# nixie_ticker.net
KiCad netlist of a schematic drawn in EAGLE
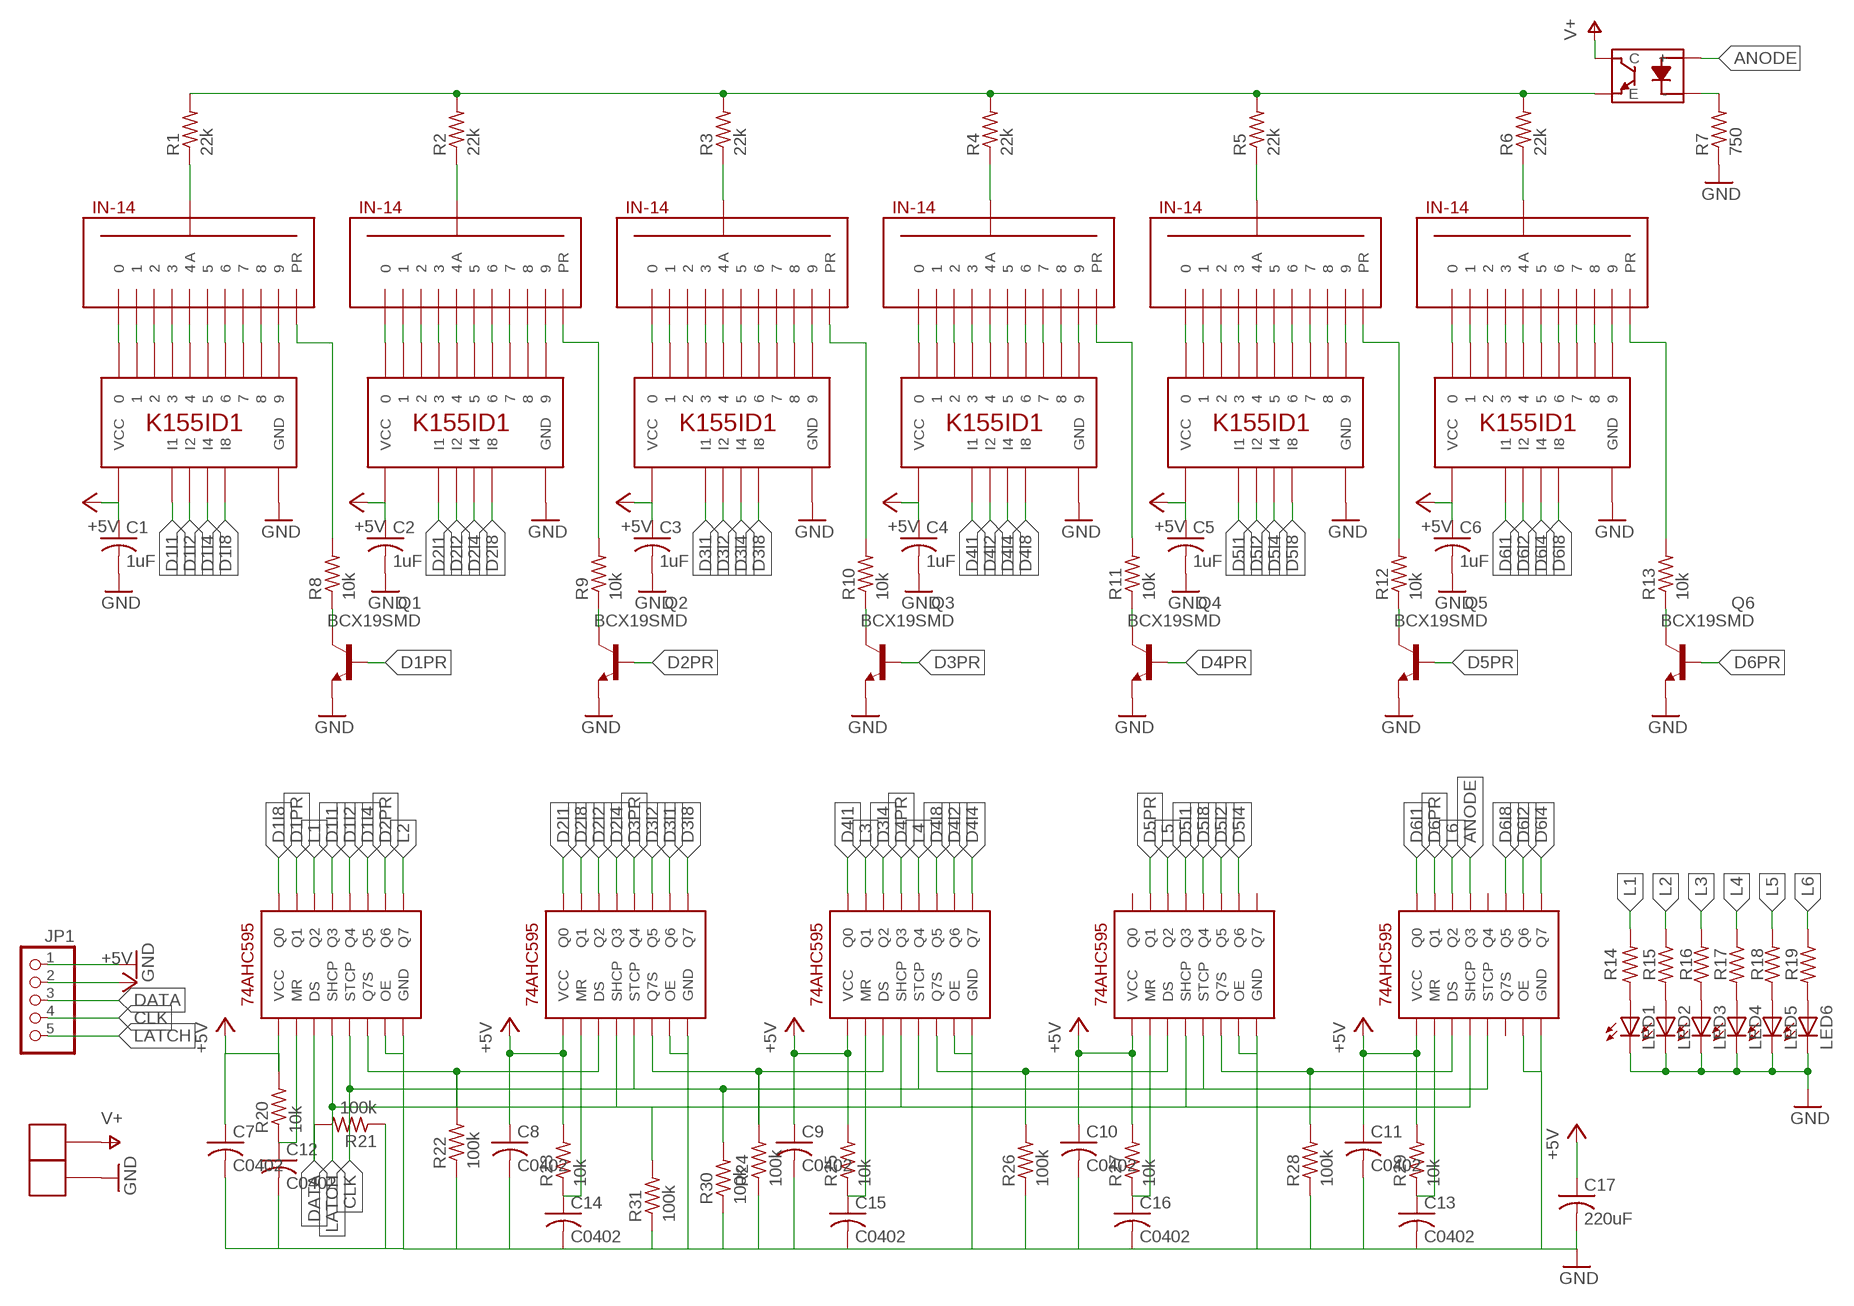
[diagram p0: schematic, sheet 1]

(export (version "E")
  (design (tool "Eeschema 10.0.6"))
  (components
    (comp (ref "C1")
      (value "1uF")
      (footprint "eagle-import:C0402")
      (libsource (lib "eagle-import") (part "C0402"))
    )
    (comp (ref "C2")
      (value "1uF")
      (footprint "eagle-import:C0402")
      (libsource (lib "eagle-import") (part "C0402"))
    )
    (comp (ref "C3")
      (value "1uF")
      (footprint "eagle-import:C0402")
      (libsource (lib "eagle-import") (part "C0402"))
    )
    (comp (ref "C4")
      (value "1uF")
      (footprint "eagle-import:C0402")
      (libsource (lib "eagle-import") (part "C0402"))
    )
    (comp (ref "C5")
      (value "1uF")
      (footprint "eagle-import:C0402")
      (libsource (lib "eagle-import") (part "C0402"))
    )
    (comp (ref "C6")
      (value "1uF")
      (footprint "eagle-import:C0402")
      (libsource (lib "eagle-import") (part "C0402"))
    )
    (comp (ref "C7")
      (value "C0402")
      (footprint "eagle-import:C0402")
      (libsource (lib "eagle-import") (part "C0402"))
    )
    (comp (ref "C8")
      (value "C0402")
      (footprint "eagle-import:C0402")
      (libsource (lib "eagle-import") (part "C0402"))
    )
    (comp (ref "C9")
      (value "C0402")
      (footprint "eagle-import:C0402")
      (libsource (lib "eagle-import") (part "C0402"))
    )
    (comp (ref "C10")
      (value "C0402")
      (footprint "eagle-import:C0402")
      (libsource (lib "eagle-import") (part "C0402"))
    )
    (comp (ref "C11")
      (value "C0402")
      (footprint "eagle-import:C0402")
      (libsource (lib "eagle-import") (part "C0402"))
    )
    (comp (ref "C12")
      (value "C0402")
      (footprint "eagle-import:C0402")
      (libsource (lib "eagle-import") (part "C0402"))
    )
    (comp (ref "C13")
      (value "C0402")
      (footprint "eagle-import:C0402")
      (libsource (lib "eagle-import") (part "C0402"))
    )
    (comp (ref "C14")
      (value "C0402")
      (footprint "eagle-import:C0402")
      (libsource (lib "eagle-import") (part "C0402"))
    )
    (comp (ref "C15")
      (value "C0402")
      (footprint "eagle-import:C0402")
      (libsource (lib "eagle-import") (part "C0402"))
    )
    (comp (ref "C16")
      (value "C0402")
      (footprint "eagle-import:C0402")
      (libsource (lib "eagle-import") (part "C0402"))
    )
    (comp (ref "C17")
      (value "220uF")
      (footprint "eagle-import:CAPAE830X1050")
      (libsource (lib "eagle-import") (part "UUR1C221MCL6GS"))
    )
    (comp (ref "JP1")
      (value "PINHD-1X5")
      (footprint "eagle-import:1X05")
      (libsource (lib "eagle-import") (part "PINHD-1X5"))
    )
    (comp (ref "JP2")
      (value "ZKFDS")
      (footprint "eagle-import:ZKFDS")
      (libsource (lib "eagle-import") (part "ZKFDS"))
    )
    (comp (ref "JP3")
      (value "ZKFDS")
      (footprint "eagle-import:ZKFDS")
      (libsource (lib "eagle-import") (part "ZKFDS"))
    )
    (comp (ref "LED1")
      (value "LEDCHIP-LED0603")
      (footprint "eagle-import:CHIP-LED0603")
      (libsource (lib "eagle-import") (part "LEDCHIP-LED0603"))
    )
    (comp (ref "LED2")
      (value "LEDCHIP-LED0603")
      (footprint "eagle-import:CHIP-LED0603")
      (libsource (lib "eagle-import") (part "LEDCHIP-LED0603"))
    )
    (comp (ref "LED3")
      (value "LEDCHIP-LED0603")
      (footprint "eagle-import:CHIP-LED0603")
      (libsource (lib "eagle-import") (part "LEDCHIP-LED0603"))
    )
    (comp (ref "LED4")
      (value "LEDCHIP-LED0603")
      (footprint "eagle-import:CHIP-LED0603")
      (libsource (lib "eagle-import") (part "LEDCHIP-LED0603"))
    )
    (comp (ref "LED5")
      (value "LEDCHIP-LED0603")
      (footprint "eagle-import:CHIP-LED0603")
      (libsource (lib "eagle-import") (part "LEDCHIP-LED0603"))
    )
    (comp (ref "LED6")
      (value "LEDCHIP-LED0603")
      (footprint "eagle-import:CHIP-LED0603")
      (libsource (lib "eagle-import") (part "LEDCHIP-LED0603"))
    )
    (comp (ref "N1")
      (value "IN14_12PIN12PIN")
      (footprint "eagle-import:IN14-12PIN")
      (libsource (lib "eagle-import") (part "IN14_12PIN12PIN"))
    )
    (comp (ref "N2")
      (value "IN14_12PIN12PIN")
      (footprint "eagle-import:IN14-12PIN")
      (libsource (lib "eagle-import") (part "IN14_12PIN12PIN"))
    )
    (comp (ref "N3")
      (value "IN14_12PIN12PIN")
      (footprint "eagle-import:IN14-12PIN")
      (libsource (lib "eagle-import") (part "IN14_12PIN12PIN"))
    )
    (comp (ref "N4")
      (value "IN14_12PIN12PIN")
      (footprint "eagle-import:IN14-12PIN")
      (libsource (lib "eagle-import") (part "IN14_12PIN12PIN"))
    )
    (comp (ref "N5")
      (value "IN14_12PIN12PIN")
      (footprint "eagle-import:IN14-12PIN")
      (libsource (lib "eagle-import") (part "IN14_12PIN12PIN"))
    )
    (comp (ref "N6")
      (value "IN14_12PIN12PIN")
      (footprint "eagle-import:IN14-12PIN")
      (libsource (lib "eagle-import") (part "IN14_12PIN12PIN"))
    )
    (comp (ref "Q1")
      (value "BCX19SMD")
      (footprint "eagle-import:SOT23-BEC")
      (libsource (lib "eagle-import") (part "BCX19SMD"))
    )
    (comp (ref "Q2")
      (value "BCX19SMD")
      (footprint "eagle-import:SOT23-BEC")
      (libsource (lib "eagle-import") (part "BCX19SMD"))
    )
    (comp (ref "Q3")
      (value "BCX19SMD")
      (footprint "eagle-import:SOT23-BEC")
      (libsource (lib "eagle-import") (part "BCX19SMD"))
    )
    (comp (ref "Q4")
      (value "BCX19SMD")
      (footprint "eagle-import:SOT23-BEC")
      (libsource (lib "eagle-import") (part "BCX19SMD"))
    )
    (comp (ref "Q5")
      (value "BCX19SMD")
      (footprint "eagle-import:SOT23-BEC")
      (libsource (lib "eagle-import") (part "BCX19SMD"))
    )
    (comp (ref "Q6")
      (value "BCX19SMD")
      (footprint "eagle-import:SOT23-BEC")
      (libsource (lib "eagle-import") (part "BCX19SMD"))
    )
    (comp (ref "R1")
      (value "22k")
      (footprint "eagle-import:R1206")
      (libsource (lib "eagle-import") (part "R-US_R1206"))
    )
    (comp (ref "R2")
      (value "22k")
      (footprint "eagle-import:R1206")
      (libsource (lib "eagle-import") (part "R-US_R1206"))
    )
    (comp (ref "R3")
      (value "22k")
      (footprint "eagle-import:R1206")
      (libsource (lib "eagle-import") (part "R-US_R1206"))
    )
    (comp (ref "R4")
      (value "22k")
      (footprint "eagle-import:R1206")
      (libsource (lib "eagle-import") (part "R-US_R1206"))
    )
    (comp (ref "R5")
      (value "22k")
      (footprint "eagle-import:R1206")
      (libsource (lib "eagle-import") (part "R-US_R1206"))
    )
    (comp (ref "R6")
      (value "22k")
      (footprint "eagle-import:R1206")
      (libsource (lib "eagle-import") (part "R-US_R1206"))
    )
    (comp (ref "R7")
      (value "750")
      (footprint "eagle-import:R0603")
      (libsource (lib "eagle-import") (part "R-US_R0603"))
    )
    (comp (ref "R8")
      (value "10k")
      (footprint "eagle-import:R0805")
      (libsource (lib "eagle-import") (part "R-US_R0805"))
    )
    (comp (ref "R9")
      (value "10k")
      (footprint "eagle-import:R0805")
      (libsource (lib "eagle-import") (part "R-US_R0805"))
    )
    (comp (ref "R10")
      (value "10k")
      (footprint "eagle-import:R0805")
      (libsource (lib "eagle-import") (part "R-US_R0805"))
    )
    (comp (ref "R11")
      (value "10k")
      (footprint "eagle-import:R0805")
      (libsource (lib "eagle-import") (part "R-US_R0805"))
    )
    (comp (ref "R12")
      (value "10k")
      (footprint "eagle-import:R0805")
      (libsource (lib "eagle-import") (part "R-US_R0805"))
    )
    (comp (ref "R13")
      (value "10k")
      (footprint "eagle-import:R0805")
      (libsource (lib "eagle-import") (part "R-US_R0805"))
    )
    (comp (ref "R14")
      (value "R-US_R0805")
      (footprint "eagle-import:R0805")
      (libsource (lib "eagle-import") (part "R-US_R0805"))
    )
    (comp (ref "R15")
      (value "R-US_R0805")
      (footprint "eagle-import:R0805")
      (libsource (lib "eagle-import") (part "R-US_R0805"))
    )
    (comp (ref "R16")
      (value "R-US_R0805")
      (footprint "eagle-import:R0805")
      (libsource (lib "eagle-import") (part "R-US_R0805"))
    )
    (comp (ref "R17")
      (value "R-US_R0805")
      (footprint "eagle-import:R0805")
      (libsource (lib "eagle-import") (part "R-US_R0805"))
    )
    (comp (ref "R18")
      (value "R-US_R0805")
      (footprint "eagle-import:R0805")
      (libsource (lib "eagle-import") (part "R-US_R0805"))
    )
    (comp (ref "R19")
      (value "R-US_R0805")
      (footprint "eagle-import:R0805")
      (libsource (lib "eagle-import") (part "R-US_R0805"))
    )
    (comp (ref "R20")
      (value "10k")
      (footprint "eagle-import:R0402")
      (libsource (lib "eagle-import") (part "R0402"))
    )
    (comp (ref "R21")
      (value "100k")
      (footprint "eagle-import:R0402")
      (libsource (lib "eagle-import") (part "R0402"))
    )
    (comp (ref "R22")
      (value "100k")
      (footprint "eagle-import:R0402")
      (libsource (lib "eagle-import") (part "R0402"))
    )
    (comp (ref "R23")
      (value "10k")
      (footprint "eagle-import:R0402")
      (libsource (lib "eagle-import") (part "R0402"))
    )
    (comp (ref "R24")
      (value "100k")
      (footprint "eagle-import:R0402")
      (libsource (lib "eagle-import") (part "R0402"))
    )
    (comp (ref "R25")
      (value "10k")
      (footprint "eagle-import:R0402")
      (libsource (lib "eagle-import") (part "R0402"))
    )
    (comp (ref "R26")
      (value "100k")
      (footprint "eagle-import:R0402")
      (libsource (lib "eagle-import") (part "R0402"))
    )
    (comp (ref "R27")
      (value "10k")
      (footprint "eagle-import:R0402")
      (libsource (lib "eagle-import") (part "R0402"))
    )
    (comp (ref "R28")
      (value "100k")
      (footprint "eagle-import:R0402")
      (libsource (lib "eagle-import") (part "R0402"))
    )
    (comp (ref "R29")
      (value "10k")
      (footprint "eagle-import:R0402")
      (libsource (lib "eagle-import") (part "R0402"))
    )
    (comp (ref "R30")
      (value "100k")
      (footprint "eagle-import:R0402")
      (libsource (lib "eagle-import") (part "R0402"))
    )
    (comp (ref "R31")
      (value "100k")
      (footprint "eagle-import:R0402")
      (libsource (lib "eagle-import") (part "R0402"))
    )
    (comp (ref "U1")
      (value "TLP3873D")
      (footprint "eagle-import:SOP254P1000X215-4")
      (libsource (lib "eagle-import") (part "TLP3873D"))
    )
    (comp (ref "U2")
      (value "K155ID1")
      (footprint "eagle-import:DIP-16_SMD")
      (libsource (lib "eagle-import") (part "K155ID1"))
    )
    (comp (ref "U3")
      (value "K155ID1")
      (footprint "eagle-import:DIP-16_SMD")
      (libsource (lib "eagle-import") (part "K155ID1"))
    )
    (comp (ref "U4")
      (value "K155ID1")
      (footprint "eagle-import:DIP-16_SMD")
      (libsource (lib "eagle-import") (part "K155ID1"))
    )
    (comp (ref "U5")
      (value "K155ID1")
      (footprint "eagle-import:DIP-16_SMD")
      (libsource (lib "eagle-import") (part "K155ID1"))
    )
    (comp (ref "U6")
      (value "K155ID1")
      (footprint "eagle-import:DIP-16_SMD")
      (libsource (lib "eagle-import") (part "K155ID1"))
    )
    (comp (ref "U7")
      (value "K155ID1")
      (footprint "eagle-import:DIP-16_SMD")
      (libsource (lib "eagle-import") (part "K155ID1"))
    )
    (comp (ref "U8")
      (value "74AHC595")
      (footprint "eagle-import:16SOIC")
      (libsource (lib "eagle-import") (part "74AHC595"))
    )
    (comp (ref "U9")
      (value "74AHC595")
      (footprint "eagle-import:16SOIC")
      (libsource (lib "eagle-import") (part "74AHC595"))
    )
    (comp (ref "U10")
      (value "74AHC595")
      (footprint "eagle-import:16SOIC")
      (libsource (lib "eagle-import") (part "74AHC595"))
    )
    (comp (ref "U11")
      (value "74AHC595")
      (footprint "eagle-import:16SOIC")
      (libsource (lib "eagle-import") (part "74AHC595"))
    )
    (comp (ref "U12")
      (value "74AHC595")
      (footprint "eagle-import:16SOIC")
      (libsource (lib "eagle-import") (part "74AHC595"))
    )
  )
  (nets
    (net (code "1") (name "+5V") (class "Default")
      (node (ref "C1") (pin "1") (pinfunction "+_1") (pintype "passive"))
      (node (ref "C10") (pin "1") (pinfunction "+_1") (pintype "passive"))
      (node (ref "C11") (pin "1") (pinfunction "+_1") (pintype "passive"))
      (node (ref "C17") (pin "1") (pinfunction "+_1") (pintype "passive"))
      (node (ref "C2") (pin "1") (pinfunction "+_1") (pintype "passive"))
      (node (ref "C3") (pin "1") (pinfunction "+_1") (pintype "passive"))
      (node (ref "C4") (pin "1") (pinfunction "+_1") (pintype "passive"))
      (node (ref "C5") (pin "1") (pinfunction "+_1") (pintype "passive"))
      (node (ref "C6") (pin "1") (pinfunction "+_1") (pintype "passive"))
      (node (ref "C7") (pin "1") (pinfunction "+_1") (pintype "passive"))
      (node (ref "C8") (pin "1") (pinfunction "+_1") (pintype "passive"))
      (node (ref "C9") (pin "1") (pinfunction "+_1") (pintype "passive"))
      (node (ref "JP1") (pin "2") (pinfunction "2_2") (pintype "passive"))
      (node (ref "R20") (pin "2") (pinfunction "2_2") (pintype "passive"))
      (node (ref "R23") (pin "2") (pinfunction "2_2") (pintype "passive"))
      (node (ref "R25") (pin "2") (pinfunction "2_2") (pintype "passive"))
      (node (ref "R27") (pin "2") (pinfunction "2_2") (pintype "passive"))
      (node (ref "R29") (pin "2") (pinfunction "2_2") (pintype "passive"))
      (node (ref "U10") (pin "P$16") (pinfunction "VCC_P$16") (pintype "bidirectional"))
      (node (ref "U11") (pin "P$16") (pinfunction "VCC_P$16") (pintype "bidirectional"))
      (node (ref "U12") (pin "P$16") (pinfunction "VCC_P$16") (pintype "bidirectional"))
      (node (ref "U2") (pin "P$5") (pinfunction "VCC_P$5") (pintype "bidirectional"))
      (node (ref "U3") (pin "P$5") (pinfunction "VCC_P$5") (pintype "bidirectional"))
      (node (ref "U4") (pin "P$5") (pinfunction "VCC_P$5") (pintype "bidirectional"))
      (node (ref "U5") (pin "P$5") (pinfunction "VCC_P$5") (pintype "bidirectional"))
      (node (ref "U6") (pin "P$5") (pinfunction "VCC_P$5") (pintype "bidirectional"))
      (node (ref "U7") (pin "P$5") (pinfunction "VCC_P$5") (pintype "bidirectional"))
      (node (ref "U8") (pin "P$16") (pinfunction "VCC_P$16") (pintype "bidirectional"))
      (node (ref "U9") (pin "P$16") (pinfunction "VCC_P$16") (pintype "bidirectional"))
    )
    (net (code "2") (name "ANODE") (class "Default")
      (node (ref "U1") (pin "1") (pinfunction "+_1") (pintype "bidirectional"))
      (node (ref "U12") (pin "P$3") (pinfunction "Q3_P$3") (pintype "bidirectional"))
    )
    (net (code "3") (name "CLK") (class "Default")
      (node (ref "JP1") (pin "4") (pinfunction "4_4") (pintype "passive"))
      (node (ref "R30") (pin "2") (pinfunction "2_2") (pintype "passive"))
      (node (ref "U10") (pin "P$12") (pinfunction "STCP_P$12") (pintype "bidirectional"))
      (node (ref "U11") (pin "P$12") (pinfunction "STCP_P$12") (pintype "bidirectional"))
      (node (ref "U12") (pin "P$12") (pinfunction "STCP_P$12") (pintype "bidirectional"))
      (node (ref "U8") (pin "P$12") (pinfunction "STCP_P$12") (pintype "bidirectional"))
      (node (ref "U9") (pin "P$12") (pinfunction "STCP_P$12") (pintype "bidirectional"))
    )
    (net (code "4") (name "D1I1") (class "Default")
      (node (ref "U2") (pin "P$3") (pinfunction "I1_P$3") (pintype "bidirectional"))
      (node (ref "U8") (pin "P$3") (pinfunction "Q3_P$3") (pintype "bidirectional"))
    )
    (net (code "5") (name "D1I2") (class "Default")
      (node (ref "U2") (pin "P$6") (pinfunction "I2_P$6") (pintype "bidirectional"))
      (node (ref "U8") (pin "P$4") (pinfunction "Q4_P$4") (pintype "bidirectional"))
    )
    (net (code "6") (name "D1I4") (class "Default")
      (node (ref "U2") (pin "P$7") (pinfunction "I4_P$7") (pintype "bidirectional"))
      (node (ref "U8") (pin "P$5") (pinfunction "Q5_P$5") (pintype "bidirectional"))
    )
    (net (code "7") (name "D1I8") (class "Default")
      (node (ref "U2") (pin "P$4") (pinfunction "I8_P$4") (pintype "bidirectional"))
      (node (ref "U8") (pin "P$15") (pinfunction "Q0_P$15") (pintype "bidirectional"))
    )
    (net (code "8") (name "D1PR") (class "Default")
      (node (ref "Q1") (pin "B") (pinfunction "B_B") (pintype "passive"))
      (node (ref "U8") (pin "P$1") (pinfunction "Q1_P$1") (pintype "bidirectional"))
    )
    (net (code "9") (name "D2I1") (class "Default")
      (node (ref "U3") (pin "P$3") (pinfunction "I1_P$3") (pintype "bidirectional"))
      (node (ref "U9") (pin "P$15") (pinfunction "Q0_P$15") (pintype "bidirectional"))
    )
    (net (code "10") (name "D2I2") (class "Default")
      (node (ref "U3") (pin "P$6") (pinfunction "I2_P$6") (pintype "bidirectional"))
      (node (ref "U9") (pin "P$2") (pinfunction "Q2_P$2") (pintype "bidirectional"))
    )
    (net (code "11") (name "D2I4") (class "Default")
      (node (ref "U3") (pin "P$7") (pinfunction "I4_P$7") (pintype "bidirectional"))
      (node (ref "U9") (pin "P$3") (pinfunction "Q3_P$3") (pintype "bidirectional"))
    )
    (net (code "12") (name "D2I8") (class "Default")
      (node (ref "U3") (pin "P$4") (pinfunction "I8_P$4") (pintype "bidirectional"))
      (node (ref "U9") (pin "P$1") (pinfunction "Q1_P$1") (pintype "bidirectional"))
    )
    (net (code "13") (name "D2PR") (class "Default")
      (node (ref "Q2") (pin "B") (pinfunction "B_B") (pintype "passive"))
      (node (ref "U8") (pin "P$6") (pinfunction "Q6_P$6") (pintype "bidirectional"))
    )
    (net (code "14") (name "D3I1") (class "Default")
      (node (ref "U4") (pin "P$3") (pinfunction "I1_P$3") (pintype "bidirectional"))
      (node (ref "U9") (pin "P$6") (pinfunction "Q6_P$6") (pintype "bidirectional"))
    )
    (net (code "15") (name "D3I2") (class "Default")
      (node (ref "U4") (pin "P$6") (pinfunction "I2_P$6") (pintype "bidirectional"))
      (node (ref "U9") (pin "P$5") (pinfunction "Q5_P$5") (pintype "bidirectional"))
    )
    (net (code "16") (name "D3I4") (class "Default")
      (node (ref "U10") (pin "P$2") (pinfunction "Q2_P$2") (pintype "bidirectional"))
      (node (ref "U4") (pin "P$7") (pinfunction "I4_P$7") (pintype "bidirectional"))
    )
    (net (code "17") (name "D3I8") (class "Default")
      (node (ref "U4") (pin "P$4") (pinfunction "I8_P$4") (pintype "bidirectional"))
      (node (ref "U9") (pin "P$7") (pinfunction "Q7_P$7") (pintype "bidirectional"))
    )
    (net (code "18") (name "D3PR") (class "Default")
      (node (ref "Q3") (pin "B") (pinfunction "B_B") (pintype "passive"))
      (node (ref "U9") (pin "P$4") (pinfunction "Q4_P$4") (pintype "bidirectional"))
    )
    (net (code "19") (name "D4I1") (class "Default")
      (node (ref "U10") (pin "P$15") (pinfunction "Q0_P$15") (pintype "bidirectional"))
      (node (ref "U5") (pin "P$3") (pinfunction "I1_P$3") (pintype "bidirectional"))
    )
    (net (code "20") (name "D4I2") (class "Default")
      (node (ref "U10") (pin "P$6") (pinfunction "Q6_P$6") (pintype "bidirectional"))
      (node (ref "U5") (pin "P$6") (pinfunction "I2_P$6") (pintype "bidirectional"))
    )
    (net (code "21") (name "D4I4") (class "Default")
      (node (ref "U10") (pin "P$7") (pinfunction "Q7_P$7") (pintype "bidirectional"))
      (node (ref "U5") (pin "P$7") (pinfunction "I4_P$7") (pintype "bidirectional"))
    )
    (net (code "22") (name "D4I8") (class "Default")
      (node (ref "U10") (pin "P$5") (pinfunction "Q5_P$5") (pintype "bidirectional"))
      (node (ref "U5") (pin "P$4") (pinfunction "I8_P$4") (pintype "bidirectional"))
    )
    (net (code "23") (name "D4PR") (class "Default")
      (node (ref "Q4") (pin "B") (pinfunction "B_B") (pintype "passive"))
      (node (ref "U10") (pin "P$3") (pinfunction "Q3_P$3") (pintype "bidirectional"))
    )
    (net (code "24") (name "D5I1") (class "Default")
      (node (ref "U11") (pin "P$3") (pinfunction "Q3_P$3") (pintype "bidirectional"))
      (node (ref "U6") (pin "P$3") (pinfunction "I1_P$3") (pintype "bidirectional"))
    )
    (net (code "25") (name "D5I2") (class "Default")
      (node (ref "U11") (pin "P$5") (pinfunction "Q5_P$5") (pintype "bidirectional"))
      (node (ref "U6") (pin "P$6") (pinfunction "I2_P$6") (pintype "bidirectional"))
    )
    (net (code "26") (name "D5I4") (class "Default")
      (node (ref "U11") (pin "P$6") (pinfunction "Q6_P$6") (pintype "bidirectional"))
      (node (ref "U6") (pin "P$7") (pinfunction "I4_P$7") (pintype "bidirectional"))
    )
    (net (code "27") (name "D5I8") (class "Default")
      (node (ref "U11") (pin "P$4") (pinfunction "Q4_P$4") (pintype "bidirectional"))
      (node (ref "U6") (pin "P$4") (pinfunction "I8_P$4") (pintype "bidirectional"))
    )
    (net (code "28") (name "D5PR") (class "Default")
      (node (ref "Q5") (pin "B") (pinfunction "B_B") (pintype "passive"))
      (node (ref "U11") (pin "P$1") (pinfunction "Q1_P$1") (pintype "bidirectional"))
    )
    (net (code "29") (name "D6I1") (class "Default")
      (node (ref "U12") (pin "P$15") (pinfunction "Q0_P$15") (pintype "bidirectional"))
      (node (ref "U7") (pin "P$3") (pinfunction "I1_P$3") (pintype "bidirectional"))
    )
    (net (code "30") (name "D6I2") (class "Default")
      (node (ref "U12") (pin "P$6") (pinfunction "Q6_P$6") (pintype "bidirectional"))
      (node (ref "U7") (pin "P$6") (pinfunction "I2_P$6") (pintype "bidirectional"))
    )
    (net (code "31") (name "D6I4") (class "Default")
      (node (ref "U12") (pin "P$7") (pinfunction "Q7_P$7") (pintype "bidirectional"))
      (node (ref "U7") (pin "P$7") (pinfunction "I4_P$7") (pintype "bidirectional"))
    )
    (net (code "32") (name "D6I8") (class "Default")
      (node (ref "U12") (pin "P$5") (pinfunction "Q5_P$5") (pintype "bidirectional"))
      (node (ref "U7") (pin "P$4") (pinfunction "I8_P$4") (pintype "bidirectional"))
    )
    (net (code "33") (name "D6PR") (class "Default")
      (node (ref "Q6") (pin "B") (pinfunction "B_B") (pintype "passive"))
      (node (ref "U12") (pin "P$1") (pinfunction "Q1_P$1") (pintype "bidirectional"))
    )
    (net (code "34") (name "DATA") (class "Default")
      (node (ref "JP1") (pin "3") (pinfunction "3_3") (pintype "passive"))
      (node (ref "R21") (pin "2") (pinfunction "2_2") (pintype "passive"))
      (node (ref "U8") (pin "P$14") (pinfunction "DS_P$14") (pintype "bidirectional"))
    )
    (net (code "35") (name "GND") (class "Default")
      (node (ref "C1") (pin "2") (pinfunction "-_2") (pintype "passive"))
      (node (ref "C10") (pin "2") (pinfunction "-_2") (pintype "passive"))
      (node (ref "C11") (pin "2") (pinfunction "-_2") (pintype "passive"))
      (node (ref "C12") (pin "2") (pinfunction "-_2") (pintype "passive"))
      (node (ref "C13") (pin "2") (pinfunction "-_2") (pintype "passive"))
      (node (ref "C14") (pin "2") (pinfunction "-_2") (pintype "passive"))
      (node (ref "C15") (pin "2") (pinfunction "-_2") (pintype "passive"))
      (node (ref "C16") (pin "2") (pinfunction "-_2") (pintype "passive"))
      (node (ref "C17") (pin "2") (pinfunction "-_2") (pintype "passive"))
      (node (ref "C2") (pin "2") (pinfunction "-_2") (pintype "passive"))
      (node (ref "C3") (pin "2") (pinfunction "-_2") (pintype "passive"))
      (node (ref "C4") (pin "2") (pinfunction "-_2") (pintype "passive"))
      (node (ref "C5") (pin "2") (pinfunction "-_2") (pintype "passive"))
      (node (ref "C6") (pin "2") (pinfunction "-_2") (pintype "passive"))
      (node (ref "C7") (pin "2") (pinfunction "-_2") (pintype "passive"))
      (node (ref "C8") (pin "2") (pinfunction "-_2") (pintype "passive"))
      (node (ref "C9") (pin "2") (pinfunction "-_2") (pintype "passive"))
      (node (ref "JP1") (pin "1") (pinfunction "1_1") (pintype "passive"))
      (node (ref "JP3") (pin "P$1") (pinfunction "P$1_P$1") (pintype "bidirectional"))
      (node (ref "JP3") (pin "P$2") (pinfunction "P$1_P$2") (pintype "bidirectional"))
      (node (ref "LED1") (pin "C") (pinfunction "C_C") (pintype "passive"))
      (node (ref "LED2") (pin "C") (pinfunction "C_C") (pintype "passive"))
      (node (ref "LED3") (pin "C") (pinfunction "C_C") (pintype "passive"))
      (node (ref "LED4") (pin "C") (pinfunction "C_C") (pintype "passive"))
      (node (ref "LED5") (pin "C") (pinfunction "C_C") (pintype "passive"))
      (node (ref "LED6") (pin "C") (pinfunction "C_C") (pintype "passive"))
      (node (ref "Q1") (pin "E") (pinfunction "E_E") (pintype "passive"))
      (node (ref "Q2") (pin "E") (pinfunction "E_E") (pintype "passive"))
      (node (ref "Q3") (pin "E") (pinfunction "E_E") (pintype "passive"))
      (node (ref "Q4") (pin "E") (pinfunction "E_E") (pintype "passive"))
      (node (ref "Q5") (pin "E") (pinfunction "E_E") (pintype "passive"))
      (node (ref "Q6") (pin "E") (pinfunction "E_E") (pintype "passive"))
      (node (ref "R21") (pin "1") (pinfunction "1_1") (pintype "passive"))
      (node (ref "R22") (pin "1") (pinfunction "1_1") (pintype "passive"))
      (node (ref "R24") (pin "1") (pinfunction "1_1") (pintype "passive"))
      (node (ref "R26") (pin "1") (pinfunction "1_1") (pintype "passive"))
      (node (ref "R28") (pin "1") (pinfunction "1_1") (pintype "passive"))
      (node (ref "R30") (pin "1") (pinfunction "1_1") (pintype "passive"))
      (node (ref "R31") (pin "1") (pinfunction "1_1") (pintype "passive"))
      (node (ref "R7") (pin "1") (pinfunction "1_1") (pintype "passive"))
      (node (ref "U10") (pin "P$13") (pinfunction "OE_P$13") (pintype "bidirectional"))
      (node (ref "U10") (pin "P$8") (pinfunction "GND_P$8") (pintype "bidirectional"))
      (node (ref "U11") (pin "P$13") (pinfunction "OE_P$13") (pintype "bidirectional"))
      (node (ref "U11") (pin "P$8") (pinfunction "GND_P$8") (pintype "bidirectional"))
      (node (ref "U12") (pin "P$13") (pinfunction "OE_P$13") (pintype "bidirectional"))
      (node (ref "U12") (pin "P$8") (pinfunction "GND_P$8") (pintype "bidirectional"))
      (node (ref "U2") (pin "P$12") (pinfunction "GND_P$12") (pintype "bidirectional"))
      (node (ref "U3") (pin "P$12") (pinfunction "GND_P$12") (pintype "bidirectional"))
      (node (ref "U4") (pin "P$12") (pinfunction "GND_P$12") (pintype "bidirectional"))
      (node (ref "U5") (pin "P$12") (pinfunction "GND_P$12") (pintype "bidirectional"))
      (node (ref "U6") (pin "P$12") (pinfunction "GND_P$12") (pintype "bidirectional"))
      (node (ref "U7") (pin "P$12") (pinfunction "GND_P$12") (pintype "bidirectional"))
      (node (ref "U8") (pin "P$13") (pinfunction "OE_P$13") (pintype "bidirectional"))
      (node (ref "U8") (pin "P$8") (pinfunction "GND_P$8") (pintype "bidirectional"))
      (node (ref "U9") (pin "P$13") (pinfunction "OE_P$13") (pintype "bidirectional"))
      (node (ref "U9") (pin "P$8") (pinfunction "GND_P$8") (pintype "bidirectional"))
    )
    (net (code "36") (name "L1") (class "Default")
      (node (ref "R14") (pin "2") (pinfunction "2_2") (pintype "passive"))
      (node (ref "U8") (pin "P$2") (pinfunction "Q2_P$2") (pintype "bidirectional"))
    )
    (net (code "37") (name "L2") (class "Default")
      (node (ref "R15") (pin "1") (pinfunction "1_1") (pintype "passive"))
      (node (ref "U8") (pin "P$7") (pinfunction "Q7_P$7") (pintype "bidirectional"))
    )
    (net (code "38") (name "L3") (class "Default")
      (node (ref "R16") (pin "2") (pinfunction "2_2") (pintype "passive"))
      (node (ref "U10") (pin "P$1") (pinfunction "Q1_P$1") (pintype "bidirectional"))
    )
    (net (code "39") (name "L4") (class "Default")
      (node (ref "R17") (pin "1") (pinfunction "1_1") (pintype "passive"))
      (node (ref "U10") (pin "P$4") (pinfunction "Q4_P$4") (pintype "bidirectional"))
    )
    (net (code "40") (name "L5") (class "Default")
      (node (ref "R18") (pin "2") (pinfunction "2_2") (pintype "passive"))
      (node (ref "U11") (pin "P$2") (pinfunction "Q2_P$2") (pintype "bidirectional"))
    )
    (net (code "41") (name "L6") (class "Default")
      (node (ref "R19") (pin "1") (pinfunction "1_1") (pintype "passive"))
      (node (ref "U12") (pin "P$2") (pinfunction "Q2_P$2") (pintype "bidirectional"))
    )
    (net (code "42") (name "LATCH") (class "Default")
      (node (ref "JP1") (pin "5") (pinfunction "5_5") (pintype "passive"))
      (node (ref "R31") (pin "2") (pinfunction "2_2") (pintype "passive"))
      (node (ref "U10") (pin "P$11") (pinfunction "SHCP_P$11") (pintype "bidirectional"))
      (node (ref "U11") (pin "P$11") (pinfunction "SHCP_P$11") (pintype "bidirectional"))
      (node (ref "U12") (pin "P$11") (pinfunction "SHCP_P$11") (pintype "bidirectional"))
      (node (ref "U8") (pin "P$11") (pinfunction "SHCP_P$11") (pintype "bidirectional"))
      (node (ref "U9") (pin "P$11") (pinfunction "SHCP_P$11") (pintype "bidirectional"))
    )
    (net (code "43") (name "Net-(C12-+)") (class "Default")
      (node (ref "C12") (pin "1") (pinfunction "+_1") (pintype "passive"))
      (node (ref "R20") (pin "1") (pinfunction "1_1") (pintype "passive"))
      (node (ref "U8") (pin "P$10") (pinfunction "MR_P$10") (pintype "bidirectional"))
    )
    (net (code "44") (name "Net-(C13-+)") (class "Default")
      (node (ref "C13") (pin "1") (pinfunction "+_1") (pintype "passive"))
      (node (ref "R29") (pin "1") (pinfunction "1_1") (pintype "passive"))
      (node (ref "U12") (pin "P$10") (pinfunction "MR_P$10") (pintype "bidirectional"))
    )
    (net (code "45") (name "Net-(C14-+)") (class "Default")
      (node (ref "C14") (pin "1") (pinfunction "+_1") (pintype "passive"))
      (node (ref "R23") (pin "1") (pinfunction "1_1") (pintype "passive"))
      (node (ref "U9") (pin "P$10") (pinfunction "MR_P$10") (pintype "bidirectional"))
    )
    (net (code "46") (name "Net-(C15-+)") (class "Default")
      (node (ref "C15") (pin "1") (pinfunction "+_1") (pintype "passive"))
      (node (ref "R25") (pin "1") (pinfunction "1_1") (pintype "passive"))
      (node (ref "U10") (pin "P$10") (pinfunction "MR_P$10") (pintype "bidirectional"))
    )
    (net (code "47") (name "Net-(C16-+)") (class "Default")
      (node (ref "C16") (pin "1") (pinfunction "+_1") (pintype "passive"))
      (node (ref "R27") (pin "1") (pinfunction "1_1") (pintype "passive"))
      (node (ref "U11") (pin "P$10") (pinfunction "MR_P$10") (pintype "bidirectional"))
    )
    (net (code "48") (name "Net-(LED1-PadA)") (class "Default")
      (node (ref "LED1") (pin "A") (pinfunction "A_A") (pintype "passive"))
      (node (ref "R14") (pin "1") (pinfunction "1_1") (pintype "passive"))
    )
    (net (code "49") (name "Net-(LED2-PadA)") (class "Default")
      (node (ref "LED2") (pin "A") (pinfunction "A_A") (pintype "passive"))
      (node (ref "R15") (pin "2") (pinfunction "2_2") (pintype "passive"))
    )
    (net (code "50") (name "Net-(LED3-PadA)") (class "Default")
      (node (ref "LED3") (pin "A") (pinfunction "A_A") (pintype "passive"))
      (node (ref "R16") (pin "1") (pinfunction "1_1") (pintype "passive"))
    )
    (net (code "51") (name "Net-(LED4-PadA)") (class "Default")
      (node (ref "LED4") (pin "A") (pinfunction "A_A") (pintype "passive"))
      (node (ref "R17") (pin "2") (pinfunction "2_2") (pintype "passive"))
    )
    (net (code "52") (name "Net-(LED5-PadA)") (class "Default")
      (node (ref "LED5") (pin "A") (pinfunction "A_A") (pintype "passive"))
      (node (ref "R18") (pin "1") (pinfunction "1_1") (pintype "passive"))
    )
    (net (code "53") (name "Net-(LED6-PadA)") (class "Default")
      (node (ref "LED6") (pin "A") (pinfunction "A_A") (pintype "passive"))
      (node (ref "R19") (pin "2") (pinfunction "2_2") (pintype "passive"))
    )
    (net (code "54") (name "Net-(N1-0)") (class "Default")
      (node (ref "N1") (pin "P$12") (pinfunction "0_P$12") (pintype "bidirectional"))
      (node (ref "U2") (pin "P$16") (pinfunction "0_P$16") (pintype "bidirectional"))
    )
    (net (code "55") (name "Net-(N1-1)") (class "Default")
      (node (ref "N1") (pin "P$3") (pinfunction "1_P$3") (pintype "bidirectional"))
      (node (ref "U2") (pin "P$15") (pinfunction "1_P$15") (pintype "bidirectional"))
    )
    (net (code "56") (name "Net-(N1-2)") (class "Default")
      (node (ref "N1") (pin "P$4") (pinfunction "2_P$4") (pintype "bidirectional"))
      (node (ref "U2") (pin "P$8") (pinfunction "2_P$8") (pintype "bidirectional"))
    )
    (net (code "57") (name "Net-(N1-3)") (class "Default")
      (node (ref "N1") (pin "P$5") (pinfunction "3_P$5") (pintype "bidirectional"))
      (node (ref "U2") (pin "P$9") (pinfunction "3_P$9") (pintype "bidirectional"))
    )
    (net (code "58") (name "Net-(N1-4)") (class "Default")
      (node (ref "N1") (pin "P$6") (pinfunction "4_P$6") (pintype "bidirectional"))
      (node (ref "U2") (pin "P$13") (pinfunction "4_P$13") (pintype "bidirectional"))
    )
    (net (code "59") (name "Net-(N1-5)") (class "Default")
      (node (ref "N1") (pin "P$7") (pinfunction "5_P$7") (pintype "bidirectional"))
      (node (ref "U2") (pin "P$14") (pinfunction "5_P$14") (pintype "bidirectional"))
    )
    (net (code "60") (name "Net-(N1-6)") (class "Default")
      (node (ref "N1") (pin "P$8") (pinfunction "6_P$8") (pintype "bidirectional"))
      (node (ref "U2") (pin "P$11") (pinfunction "6_P$11") (pintype "bidirectional"))
    )
    (net (code "61") (name "Net-(N1-7)") (class "Default")
      (node (ref "N1") (pin "P$9") (pinfunction "7_P$9") (pintype "bidirectional"))
      (node (ref "U2") (pin "P$10") (pinfunction "7_P$10") (pintype "bidirectional"))
    )
    (net (code "62") (name "Net-(N1-8)") (class "Default")
      (node (ref "N1") (pin "P$10") (pinfunction "8_P$10") (pintype "bidirectional"))
      (node (ref "U2") (pin "P$1") (pinfunction "8_P$1") (pintype "bidirectional"))
    )
    (net (code "63") (name "Net-(N1-9)") (class "Default")
      (node (ref "N1") (pin "P$11") (pinfunction "9_P$11") (pintype "bidirectional"))
      (node (ref "U2") (pin "P$2") (pinfunction "9_P$2") (pintype "bidirectional"))
    )
    (net (code "64") (name "Net-(N1-A)") (class "Default")
      (node (ref "N1") (pin "P$1") (pinfunction "A_P$1") (pintype "bidirectional"))
      (node (ref "R1") (pin "1") (pinfunction "1_1") (pintype "passive"))
    )
    (net (code "65") (name "Net-(N1-PR)") (class "Default")
      (node (ref "N1") (pin "P$2") (pinfunction "PR_P$2") (pintype "bidirectional"))
      (node (ref "R8") (pin "2") (pinfunction "2_2") (pintype "passive"))
    )
    (net (code "66") (name "Net-(N2-0)") (class "Default")
      (node (ref "N2") (pin "P$12") (pinfunction "0_P$12") (pintype "bidirectional"))
      (node (ref "U3") (pin "P$16") (pinfunction "0_P$16") (pintype "bidirectional"))
    )
    (net (code "67") (name "Net-(N2-1)") (class "Default")
      (node (ref "N2") (pin "P$3") (pinfunction "1_P$3") (pintype "bidirectional"))
      (node (ref "U3") (pin "P$15") (pinfunction "1_P$15") (pintype "bidirectional"))
    )
    (net (code "68") (name "Net-(N2-2)") (class "Default")
      (node (ref "N2") (pin "P$4") (pinfunction "2_P$4") (pintype "bidirectional"))
      (node (ref "U3") (pin "P$8") (pinfunction "2_P$8") (pintype "bidirectional"))
    )
    (net (code "69") (name "Net-(N2-3)") (class "Default")
      (node (ref "N2") (pin "P$5") (pinfunction "3_P$5") (pintype "bidirectional"))
      (node (ref "U3") (pin "P$9") (pinfunction "3_P$9") (pintype "bidirectional"))
    )
    (net (code "70") (name "Net-(N2-4)") (class "Default")
      (node (ref "N2") (pin "P$6") (pinfunction "4_P$6") (pintype "bidirectional"))
      (node (ref "U3") (pin "P$13") (pinfunction "4_P$13") (pintype "bidirectional"))
    )
    (net (code "71") (name "Net-(N2-5)") (class "Default")
      (node (ref "N2") (pin "P$7") (pinfunction "5_P$7") (pintype "bidirectional"))
      (node (ref "U3") (pin "P$14") (pinfunction "5_P$14") (pintype "bidirectional"))
    )
    (net (code "72") (name "Net-(N2-6)") (class "Default")
      (node (ref "N2") (pin "P$8") (pinfunction "6_P$8") (pintype "bidirectional"))
      (node (ref "U3") (pin "P$11") (pinfunction "6_P$11") (pintype "bidirectional"))
    )
    (net (code "73") (name "Net-(N2-7)") (class "Default")
      (node (ref "N2") (pin "P$9") (pinfunction "7_P$9") (pintype "bidirectional"))
      (node (ref "U3") (pin "P$10") (pinfunction "7_P$10") (pintype "bidirectional"))
    )
    (net (code "74") (name "Net-(N2-8)") (class "Default")
      (node (ref "N2") (pin "P$10") (pinfunction "8_P$10") (pintype "bidirectional"))
      (node (ref "U3") (pin "P$1") (pinfunction "8_P$1") (pintype "bidirectional"))
    )
    (net (code "75") (name "Net-(N2-9)") (class "Default")
      (node (ref "N2") (pin "P$11") (pinfunction "9_P$11") (pintype "bidirectional"))
      (node (ref "U3") (pin "P$2") (pinfunction "9_P$2") (pintype "bidirectional"))
    )
    (net (code "76") (name "Net-(N2-A)") (class "Default")
      (node (ref "N2") (pin "P$1") (pinfunction "A_P$1") (pintype "bidirectional"))
      (node (ref "R2") (pin "1") (pinfunction "1_1") (pintype "passive"))
    )
    (net (code "77") (name "Net-(N2-PR)") (class "Default")
      (node (ref "N2") (pin "P$2") (pinfunction "PR_P$2") (pintype "bidirectional"))
      (node (ref "R9") (pin "2") (pinfunction "2_2") (pintype "passive"))
    )
    (net (code "78") (name "Net-(N3-0)") (class "Default")
      (node (ref "N3") (pin "P$12") (pinfunction "0_P$12") (pintype "bidirectional"))
      (node (ref "U4") (pin "P$16") (pinfunction "0_P$16") (pintype "bidirectional"))
    )
    (net (code "79") (name "Net-(N3-1)") (class "Default")
      (node (ref "N3") (pin "P$3") (pinfunction "1_P$3") (pintype "bidirectional"))
      (node (ref "U4") (pin "P$15") (pinfunction "1_P$15") (pintype "bidirectional"))
    )
    (net (code "80") (name "Net-(N3-2)") (class "Default")
      (node (ref "N3") (pin "P$4") (pinfunction "2_P$4") (pintype "bidirectional"))
      (node (ref "U4") (pin "P$8") (pinfunction "2_P$8") (pintype "bidirectional"))
    )
    (net (code "81") (name "Net-(N3-3)") (class "Default")
      (node (ref "N3") (pin "P$5") (pinfunction "3_P$5") (pintype "bidirectional"))
      (node (ref "U4") (pin "P$9") (pinfunction "3_P$9") (pintype "bidirectional"))
    )
    (net (code "82") (name "Net-(N3-4)") (class "Default")
      (node (ref "N3") (pin "P$6") (pinfunction "4_P$6") (pintype "bidirectional"))
      (node (ref "U4") (pin "P$13") (pinfunction "4_P$13") (pintype "bidirectional"))
    )
    (net (code "83") (name "Net-(N3-5)") (class "Default")
      (node (ref "N3") (pin "P$7") (pinfunction "5_P$7") (pintype "bidirectional"))
      (node (ref "U4") (pin "P$14") (pinfunction "5_P$14") (pintype "bidirectional"))
    )
    (net (code "84") (name "Net-(N3-6)") (class "Default")
      (node (ref "N3") (pin "P$8") (pinfunction "6_P$8") (pintype "bidirectional"))
      (node (ref "U4") (pin "P$11") (pinfunction "6_P$11") (pintype "bidirectional"))
    )
    (net (code "85") (name "Net-(N3-7)") (class "Default")
      (node (ref "N3") (pin "P$9") (pinfunction "7_P$9") (pintype "bidirectional"))
      (node (ref "U4") (pin "P$10") (pinfunction "7_P$10") (pintype "bidirectional"))
    )
    (net (code "86") (name "Net-(N3-8)") (class "Default")
      (node (ref "N3") (pin "P$10") (pinfunction "8_P$10") (pintype "bidirectional"))
      (node (ref "U4") (pin "P$1") (pinfunction "8_P$1") (pintype "bidirectional"))
    )
    (net (code "87") (name "Net-(N3-9)") (class "Default")
      (node (ref "N3") (pin "P$11") (pinfunction "9_P$11") (pintype "bidirectional"))
      (node (ref "U4") (pin "P$2") (pinfunction "9_P$2") (pintype "bidirectional"))
    )
    (net (code "88") (name "Net-(N3-A)") (class "Default")
      (node (ref "N3") (pin "P$1") (pinfunction "A_P$1") (pintype "bidirectional"))
      (node (ref "R3") (pin "1") (pinfunction "1_1") (pintype "passive"))
    )
    (net (code "89") (name "Net-(N3-PR)") (class "Default")
      (node (ref "N3") (pin "P$2") (pinfunction "PR_P$2") (pintype "bidirectional"))
      (node (ref "R10") (pin "2") (pinfunction "2_2") (pintype "passive"))
    )
    (net (code "90") (name "Net-(N4-0)") (class "Default")
      (node (ref "N4") (pin "P$12") (pinfunction "0_P$12") (pintype "bidirectional"))
      (node (ref "U5") (pin "P$16") (pinfunction "0_P$16") (pintype "bidirectional"))
    )
    (net (code "91") (name "Net-(N4-1)") (class "Default")
      (node (ref "N4") (pin "P$3") (pinfunction "1_P$3") (pintype "bidirectional"))
      (node (ref "U5") (pin "P$15") (pinfunction "1_P$15") (pintype "bidirectional"))
    )
    (net (code "92") (name "Net-(N4-2)") (class "Default")
      (node (ref "N4") (pin "P$4") (pinfunction "2_P$4") (pintype "bidirectional"))
      (node (ref "U5") (pin "P$8") (pinfunction "2_P$8") (pintype "bidirectional"))
    )
    (net (code "93") (name "Net-(N4-3)") (class "Default")
      (node (ref "N4") (pin "P$5") (pinfunction "3_P$5") (pintype "bidirectional"))
      (node (ref "U5") (pin "P$9") (pinfunction "3_P$9") (pintype "bidirectional"))
    )
    (net (code "94") (name "Net-(N4-4)") (class "Default")
      (node (ref "N4") (pin "P$6") (pinfunction "4_P$6") (pintype "bidirectional"))
      (node (ref "U5") (pin "P$13") (pinfunction "4_P$13") (pintype "bidirectional"))
    )
    (net (code "95") (name "Net-(N4-5)") (class "Default")
      (node (ref "N4") (pin "P$7") (pinfunction "5_P$7") (pintype "bidirectional"))
      (node (ref "U5") (pin "P$14") (pinfunction "5_P$14") (pintype "bidirectional"))
    )
    (net (code "96") (name "Net-(N4-6)") (class "Default")
      (node (ref "N4") (pin "P$8") (pinfunction "6_P$8") (pintype "bidirectional"))
      (node (ref "U5") (pin "P$11") (pinfunction "6_P$11") (pintype "bidirectional"))
    )
    (net (code "97") (name "Net-(N4-7)") (class "Default")
      (node (ref "N4") (pin "P$9") (pinfunction "7_P$9") (pintype "bidirectional"))
      (node (ref "U5") (pin "P$10") (pinfunction "7_P$10") (pintype "bidirectional"))
    )
    (net (code "98") (name "Net-(N4-8)") (class "Default")
      (node (ref "N4") (pin "P$10") (pinfunction "8_P$10") (pintype "bidirectional"))
      (node (ref "U5") (pin "P$1") (pinfunction "8_P$1") (pintype "bidirectional"))
    )
    (net (code "99") (name "Net-(N4-9)") (class "Default")
      (node (ref "N4") (pin "P$11") (pinfunction "9_P$11") (pintype "bidirectional"))
      (node (ref "U5") (pin "P$2") (pinfunction "9_P$2") (pintype "bidirectional"))
    )
    (net (code "100") (name "Net-(N4-A)") (class "Default")
      (node (ref "N4") (pin "P$1") (pinfunction "A_P$1") (pintype "bidirectional"))
      (node (ref "R4") (pin "1") (pinfunction "1_1") (pintype "passive"))
    )
    (net (code "101") (name "Net-(N4-PR)") (class "Default")
      (node (ref "N4") (pin "P$2") (pinfunction "PR_P$2") (pintype "bidirectional"))
      (node (ref "R11") (pin "2") (pinfunction "2_2") (pintype "passive"))
    )
    (net (code "102") (name "Net-(N5-0)") (class "Default")
      (node (ref "N5") (pin "P$12") (pinfunction "0_P$12") (pintype "bidirectional"))
      (node (ref "U6") (pin "P$16") (pinfunction "0_P$16") (pintype "bidirectional"))
    )
    (net (code "103") (name "Net-(N5-1)") (class "Default")
      (node (ref "N5") (pin "P$3") (pinfunction "1_P$3") (pintype "bidirectional"))
      (node (ref "U6") (pin "P$15") (pinfunction "1_P$15") (pintype "bidirectional"))
    )
    (net (code "104") (name "Net-(N5-2)") (class "Default")
      (node (ref "N5") (pin "P$4") (pinfunction "2_P$4") (pintype "bidirectional"))
      (node (ref "U6") (pin "P$8") (pinfunction "2_P$8") (pintype "bidirectional"))
    )
    (net (code "105") (name "Net-(N5-3)") (class "Default")
      (node (ref "N5") (pin "P$5") (pinfunction "3_P$5") (pintype "bidirectional"))
      (node (ref "U6") (pin "P$9") (pinfunction "3_P$9") (pintype "bidirectional"))
    )
    (net (code "106") (name "Net-(N5-4)") (class "Default")
      (node (ref "N5") (pin "P$6") (pinfunction "4_P$6") (pintype "bidirectional"))
      (node (ref "U6") (pin "P$13") (pinfunction "4_P$13") (pintype "bidirectional"))
    )
    (net (code "107") (name "Net-(N5-5)") (class "Default")
      (node (ref "N5") (pin "P$7") (pinfunction "5_P$7") (pintype "bidirectional"))
      (node (ref "U6") (pin "P$14") (pinfunction "5_P$14") (pintype "bidirectional"))
    )
    (net (code "108") (name "Net-(N5-6)") (class "Default")
      (node (ref "N5") (pin "P$8") (pinfunction "6_P$8") (pintype "bidirectional"))
      (node (ref "U6") (pin "P$11") (pinfunction "6_P$11") (pintype "bidirectional"))
    )
    (net (code "109") (name "Net-(N5-7)") (class "Default")
      (node (ref "N5") (pin "P$9") (pinfunction "7_P$9") (pintype "bidirectional"))
      (node (ref "U6") (pin "P$10") (pinfunction "7_P$10") (pintype "bidirectional"))
    )
    (net (code "110") (name "Net-(N5-8)") (class "Default")
      (node (ref "N5") (pin "P$10") (pinfunction "8_P$10") (pintype "bidirectional"))
      (node (ref "U6") (pin "P$1") (pinfunction "8_P$1") (pintype "bidirectional"))
    )
    (net (code "111") (name "Net-(N5-9)") (class "Default")
      (node (ref "N5") (pin "P$11") (pinfunction "9_P$11") (pintype "bidirectional"))
      (node (ref "U6") (pin "P$2") (pinfunction "9_P$2") (pintype "bidirectional"))
    )
    (net (code "112") (name "Net-(N5-A)") (class "Default")
      (node (ref "N5") (pin "P$1") (pinfunction "A_P$1") (pintype "bidirectional"))
      (node (ref "R5") (pin "1") (pinfunction "1_1") (pintype "passive"))
    )
    (net (code "113") (name "Net-(N5-PR)") (class "Default")
      (node (ref "N5") (pin "P$2") (pinfunction "PR_P$2") (pintype "bidirectional"))
      (node (ref "R12") (pin "2") (pinfunction "2_2") (pintype "passive"))
    )
    (net (code "114") (name "Net-(N6-0)") (class "Default")
      (node (ref "N6") (pin "P$12") (pinfunction "0_P$12") (pintype "bidirectional"))
      (node (ref "U7") (pin "P$16") (pinfunction "0_P$16") (pintype "bidirectional"))
    )
    (net (code "115") (name "Net-(N6-1)") (class "Default")
      (node (ref "N6") (pin "P$3") (pinfunction "1_P$3") (pintype "bidirectional"))
      (node (ref "U7") (pin "P$15") (pinfunction "1_P$15") (pintype "bidirectional"))
    )
    (net (code "116") (name "Net-(N6-2)") (class "Default")
      (node (ref "N6") (pin "P$4") (pinfunction "2_P$4") (pintype "bidirectional"))
      (node (ref "U7") (pin "P$8") (pinfunction "2_P$8") (pintype "bidirectional"))
    )
    (net (code "117") (name "Net-(N6-3)") (class "Default")
      (node (ref "N6") (pin "P$5") (pinfunction "3_P$5") (pintype "bidirectional"))
      (node (ref "U7") (pin "P$9") (pinfunction "3_P$9") (pintype "bidirectional"))
    )
    (net (code "118") (name "Net-(N6-4)") (class "Default")
      (node (ref "N6") (pin "P$6") (pinfunction "4_P$6") (pintype "bidirectional"))
      (node (ref "U7") (pin "P$13") (pinfunction "4_P$13") (pintype "bidirectional"))
    )
    (net (code "119") (name "Net-(N6-5)") (class "Default")
      (node (ref "N6") (pin "P$7") (pinfunction "5_P$7") (pintype "bidirectional"))
      (node (ref "U7") (pin "P$14") (pinfunction "5_P$14") (pintype "bidirectional"))
    )
    (net (code "120") (name "Net-(N6-6)") (class "Default")
      (node (ref "N6") (pin "P$8") (pinfunction "6_P$8") (pintype "bidirectional"))
      (node (ref "U7") (pin "P$11") (pinfunction "6_P$11") (pintype "bidirectional"))
    )
    (net (code "121") (name "Net-(N6-7)") (class "Default")
      (node (ref "N6") (pin "P$9") (pinfunction "7_P$9") (pintype "bidirectional"))
      (node (ref "U7") (pin "P$10") (pinfunction "7_P$10") (pintype "bidirectional"))
    )
    (net (code "122") (name "Net-(N6-8)") (class "Default")
      (node (ref "N6") (pin "P$10") (pinfunction "8_P$10") (pintype "bidirectional"))
      (node (ref "U7") (pin "P$1") (pinfunction "8_P$1") (pintype "bidirectional"))
    )
    (net (code "123") (name "Net-(N6-9)") (class "Default")
      (node (ref "N6") (pin "P$11") (pinfunction "9_P$11") (pintype "bidirectional"))
      (node (ref "U7") (pin "P$2") (pinfunction "9_P$2") (pintype "bidirectional"))
    )
    (net (code "124") (name "Net-(N6-A)") (class "Default")
      (node (ref "N6") (pin "P$1") (pinfunction "A_P$1") (pintype "bidirectional"))
      (node (ref "R6") (pin "1") (pinfunction "1_1") (pintype "passive"))
    )
    (net (code "125") (name "Net-(N6-PR)") (class "Default")
      (node (ref "N6") (pin "P$2") (pinfunction "PR_P$2") (pintype "bidirectional"))
      (node (ref "R13") (pin "2") (pinfunction "2_2") (pintype "passive"))
    )
    (net (code "126") (name "Net-(Q1-PadC)") (class "Default")
      (node (ref "Q1") (pin "C") (pinfunction "C_C") (pintype "passive"))
      (node (ref "R8") (pin "1") (pinfunction "1_1") (pintype "passive"))
    )
    (net (code "127") (name "Net-(Q2-PadC)") (class "Default")
      (node (ref "Q2") (pin "C") (pinfunction "C_C") (pintype "passive"))
      (node (ref "R9") (pin "1") (pinfunction "1_1") (pintype "passive"))
    )
    (net (code "128") (name "Net-(Q3-PadC)") (class "Default")
      (node (ref "Q3") (pin "C") (pinfunction "C_C") (pintype "passive"))
      (node (ref "R10") (pin "1") (pinfunction "1_1") (pintype "passive"))
    )
    (net (code "129") (name "Net-(Q4-PadC)") (class "Default")
      (node (ref "Q4") (pin "C") (pinfunction "C_C") (pintype "passive"))
      (node (ref "R11") (pin "1") (pinfunction "1_1") (pintype "passive"))
    )
    (net (code "130") (name "Net-(Q5-PadC)") (class "Default")
      (node (ref "Q5") (pin "C") (pinfunction "C_C") (pintype "passive"))
      (node (ref "R12") (pin "1") (pinfunction "1_1") (pintype "passive"))
    )
    (net (code "131") (name "Net-(Q6-PadC)") (class "Default")
      (node (ref "Q6") (pin "C") (pinfunction "C_C") (pintype "passive"))
      (node (ref "R13") (pin "1") (pinfunction "1_1") (pintype "passive"))
    )
    (net (code "132") (name "Net-(U1--)") (class "Default")
      (node (ref "R7") (pin "2") (pinfunction "2_2") (pintype "passive"))
      (node (ref "U1") (pin "2") (pinfunction "-_2") (pintype "bidirectional"))
    )
    (net (code "133") (name "Net-(U1-E)") (class "Default")
      (node (ref "R1") (pin "2") (pinfunction "2_2") (pintype "passive"))
      (node (ref "R2") (pin "2") (pinfunction "2_2") (pintype "passive"))
      (node (ref "R3") (pin "2") (pinfunction "2_2") (pintype "passive"))
      (node (ref "R4") (pin "2") (pinfunction "2_2") (pintype "passive"))
      (node (ref "R5") (pin "2") (pinfunction "2_2") (pintype "passive"))
      (node (ref "R6") (pin "2") (pinfunction "2_2") (pintype "passive"))
      (node (ref "U1") (pin "3") (pinfunction "E_3") (pintype "bidirectional"))
    )
    (net (code "134") (name "Net-(U8-Q7S)") (class "Default")
      (node (ref "R22") (pin "2") (pinfunction "2_2") (pintype "passive"))
      (node (ref "U8") (pin "P$9") (pinfunction "Q7S_P$9") (pintype "bidirectional"))
      (node (ref "U9") (pin "P$14") (pinfunction "DS_P$14") (pintype "bidirectional"))
    )
    (net (code "135") (name "Net-(U10-DS)") (class "Default")
      (node (ref "R24") (pin "2") (pinfunction "2_2") (pintype "passive"))
      (node (ref "U10") (pin "P$14") (pinfunction "DS_P$14") (pintype "bidirectional"))
      (node (ref "U9") (pin "P$9") (pinfunction "Q7S_P$9") (pintype "bidirectional"))
    )
    (net (code "136") (name "Net-(U10-Q7S)") (class "Default")
      (node (ref "R26") (pin "2") (pinfunction "2_2") (pintype "passive"))
      (node (ref "U10") (pin "P$9") (pinfunction "Q7S_P$9") (pintype "bidirectional"))
      (node (ref "U11") (pin "P$14") (pinfunction "DS_P$14") (pintype "bidirectional"))
    )
    (net (code "137") (name "Net-(U11-Q7S)") (class "Default")
      (node (ref "R28") (pin "2") (pinfunction "2_2") (pintype "passive"))
      (node (ref "U11") (pin "P$9") (pinfunction "Q7S_P$9") (pintype "bidirectional"))
      (node (ref "U12") (pin "P$14") (pinfunction "DS_P$14") (pintype "bidirectional"))
    )
    (net (code "138") (name "V+") (class "Default")
      (node (ref "JP2") (pin "P$1") (pinfunction "P$1_P$1") (pintype "bidirectional"))
      (node (ref "JP2") (pin "P$2") (pinfunction "P$1_P$2") (pintype "bidirectional"))
      (node (ref "U1") (pin "4") (pinfunction "C_4") (pintype "bidirectional"))
    )
    (net (code "139") (name "unconnected-(U11-Q0-PadP$15)") (class "Default")
      (node (ref "U11") (pin "P$15") (pinfunction "Q0_P$15") (pintype "bidirectional"))
    )
    (net (code "140") (name "unconnected-(U11-Q7-PadP$7)") (class "Default")
      (node (ref "U11") (pin "P$7") (pinfunction "Q7_P$7") (pintype "bidirectional"))
    )
    (net (code "141") (name "unconnected-(U12-Q4-PadP$4)") (class "Default")
      (node (ref "U12") (pin "P$4") (pinfunction "Q4_P$4") (pintype "bidirectional"))
    )
    (net (code "142") (name "unconnected-(U12-Q7S-PadP$9)") (class "Default")
      (node (ref "U12") (pin "P$9") (pinfunction "Q7S_P$9") (pintype "bidirectional"))
    )
  )
)
